# canboard.net
KiCad netlist of a schematic drawn in EAGLE
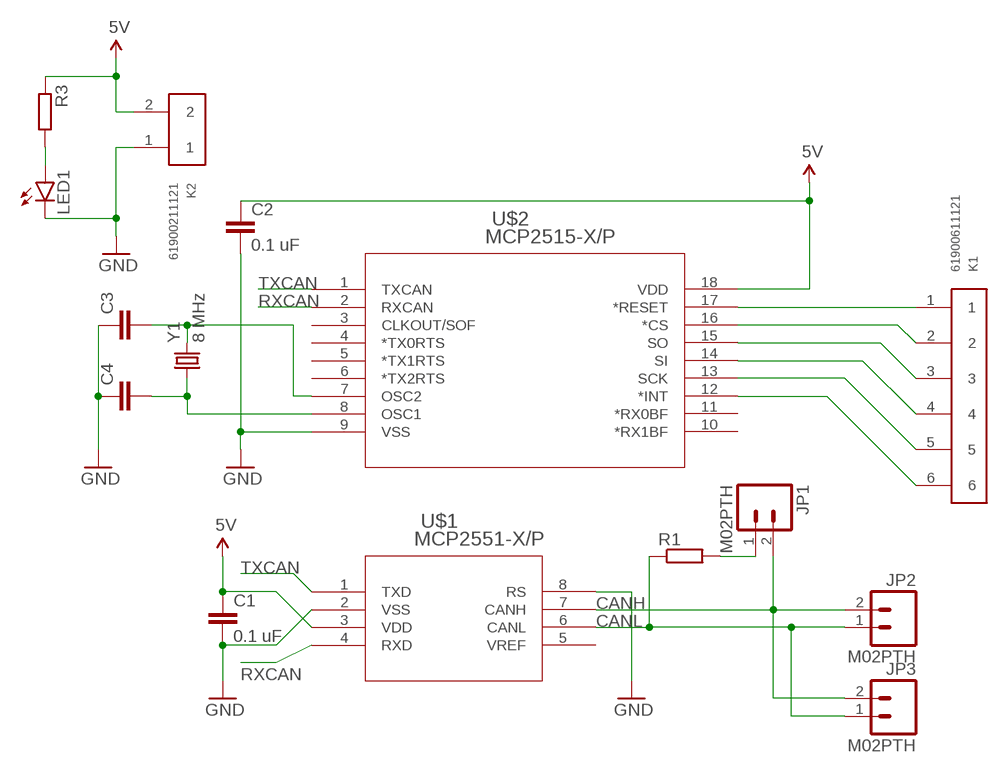
[diagram p0: schematic, sheet 1]

(export (version "E")
  (design (tool "Eeschema 10.0.6"))
  (components
    (comp (ref "C1")
      (value "0.1 uF")
      (footprint "eagle-import:C050-030X075")
      (libsource (lib "eagle-import") (part "C-EU050-030X075"))
    )
    (comp (ref "C2")
      (value "0.1 uF")
      (footprint "eagle-import:C050-030X075")
      (libsource (lib "eagle-import") (part "C-EU050-030X075"))
    )
    (comp (ref "C3")
      (value "C-EU025-025X050")
      (footprint "eagle-import:C025-025X050")
      (libsource (lib "eagle-import") (part "C-EU025-025X050"))
    )
    (comp (ref "C4")
      (value "C-EU025-025X050")
      (footprint "eagle-import:C025-025X050")
      (libsource (lib "eagle-import") (part "C-EU025-025X050"))
    )
    (comp (ref "JP1")
      (value "M02PTH")
      (footprint "eagle-import:1X02")
      (libsource (lib "eagle-import") (part "M02PTH"))
    )
    (comp (ref "JP2")
      (value "M02PTH")
      (footprint "eagle-import:1X02")
      (libsource (lib "eagle-import") (part "M02PTH"))
    )
    (comp (ref "JP3")
      (value "M02PTH")
      (footprint "eagle-import:1X02")
      (libsource (lib "eagle-import") (part "M02PTH"))
    )
    (comp (ref "K1")
      (value "61900611121")
      (footprint "eagle-import:61900611121")
      (libsource (lib "eagle-import") (part "61900611121"))
    )
    (comp (ref "K2")
      (value "61900211121")
      (footprint "eagle-import:61900211121")
      (libsource (lib "eagle-import") (part "61900211121"))
    )
    (comp (ref "LED1")
      (value "LED3MM")
      (footprint "eagle-import:LED3MM")
      (libsource (lib "eagle-import") (part "LED3MM"))
    )
    (comp (ref "R1")
      (value "R-EU_0207/10")
      (footprint "eagle-import:0207_10")
      (libsource (lib "eagle-import") (part "R-EU_0207/10"))
    )
    (comp (ref "R3")
      (value "R-EU_0207/10")
      (footprint "eagle-import:0207_10")
      (libsource (lib "eagle-import") (part "R-EU_0207/10"))
    )
    (comp (ref "U$1")
      (value "MCP2551-X/P")
      (footprint "eagle-import:PDIP8_300MC")
      (libsource (lib "eagle-import") (part "MCP2551-X/P"))
    )
    (comp (ref "U$2")
      (value "MCP2515-X/P")
      (footprint "eagle-import:PDIP18_300MC")
      (libsource (lib "eagle-import") (part "MCP2515-X/P"))
    )
    (comp (ref "Y1")
      (value "8 MHz")
      (footprint "eagle-import:HC49US")
      (libsource (lib "eagle-import") (part "CRYSTALHC49US"))
    )
  )
  (nets
    (net (code "1") (name "/CANH") (class "Default")
      (node (ref "JP1") (pin "2") (pinfunction "2_2") (pintype "passive"))
      (node (ref "JP2") (pin "2") (pinfunction "2_2") (pintype "passive"))
      (node (ref "JP3") (pin "2") (pinfunction "2_2") (pintype "passive"))
      (node (ref "U$1") (pin "7") (pinfunction "CANH_7") (pintype "passive"))
    )
    (net (code "2") (name "/CANL") (class "Default")
      (node (ref "JP2") (pin "1") (pinfunction "1_1") (pintype "passive"))
      (node (ref "JP3") (pin "1") (pinfunction "1_1") (pintype "passive"))
      (node (ref "R1") (pin "1") (pinfunction "1_1") (pintype "passive"))
      (node (ref "U$1") (pin "6") (pinfunction "CANL_6") (pintype "passive"))
    )
    (net (code "3") (name "/RXCAN") (class "Default")
      (node (ref "U$1") (pin "4") (pinfunction "RXD_4") (pintype "passive"))
      (node (ref "U$2") (pin "2") (pinfunction "RXCAN_2") (pintype "passive"))
    )
    (net (code "4") (name "/TXCAN") (class "Default")
      (node (ref "U$1") (pin "1") (pinfunction "TXD_1") (pintype "passive"))
      (node (ref "U$2") (pin "1") (pinfunction "TXCAN_1") (pintype "passive"))
    )
    (net (code "5") (name "5V") (class "Default")
      (node (ref "C1") (pin "1") (pinfunction "1_1") (pintype "passive"))
      (node (ref "C2") (pin "1") (pinfunction "1_1") (pintype "passive"))
      (node (ref "K2") (pin "2") (pinfunction "2_2") (pintype "bidirectional"))
      (node (ref "R3") (pin "1") (pinfunction "1_1") (pintype "passive"))
      (node (ref "U$1") (pin "3") (pinfunction "VDD_3") (pintype "passive"))
      (node (ref "U$2") (pin "18") (pinfunction "VDD_18") (pintype "passive"))
    )
    (net (code "6") (name "GND") (class "Default")
      (node (ref "C1") (pin "2") (pinfunction "2_2") (pintype "passive"))
      (node (ref "C2") (pin "2") (pinfunction "2_2") (pintype "passive"))
      (node (ref "C3") (pin "1") (pinfunction "1_1") (pintype "passive"))
      (node (ref "C4") (pin "1") (pinfunction "1_1") (pintype "passive"))
      (node (ref "K2") (pin "1") (pinfunction "1_1") (pintype "bidirectional"))
      (node (ref "LED1") (pin "K") (pinfunction "C_K") (pintype "passive"))
      (node (ref "U$1") (pin "2") (pinfunction "VSS_2") (pintype "passive"))
      (node (ref "U$1") (pin "8") (pinfunction "RS_8") (pintype "passive"))
      (node (ref "U$2") (pin "9") (pinfunction "VSS_9") (pintype "passive"))
    )
    (net (code "7") (name "Net-(JP1-Pad1)") (class "Default")
      (node (ref "JP1") (pin "1") (pinfunction "1_1") (pintype "passive"))
      (node (ref "R1") (pin "2") (pinfunction "2_2") (pintype "passive"))
    )
    (net (code "8") (name "Net-(LED1-PadA)") (class "Default")
      (node (ref "LED1") (pin "A") (pinfunction "A_A") (pintype "passive"))
      (node (ref "R3") (pin "2") (pinfunction "2_2") (pintype "passive"))
    )
    (net (code "9") (name "Net-(U$2-*CS)") (class "Default")
      (node (ref "K1") (pin "2") (pinfunction "2_2") (pintype "bidirectional"))
      (node (ref "U$2") (pin "16") (pinfunction "*CS_16") (pintype "passive"))
    )
    (net (code "10") (name "Net-(U$2-*INT)") (class "Default")
      (node (ref "K1") (pin "6") (pinfunction "6_6") (pintype "bidirectional"))
      (node (ref "U$2") (pin "12") (pinfunction "*INT_12") (pintype "passive"))
    )
    (net (code "11") (name "Net-(U$2-*RESET)") (class "Default")
      (node (ref "K1") (pin "1") (pinfunction "1_1") (pintype "bidirectional"))
      (node (ref "U$2") (pin "17") (pinfunction "*RESET_17") (pintype "passive"))
    )
    (net (code "12") (name "Net-(U$2-OSC1)") (class "Default")
      (node (ref "C4") (pin "2") (pinfunction "2_2") (pintype "passive"))
      (node (ref "U$2") (pin "8") (pinfunction "OSC1_8") (pintype "passive"))
      (node (ref "Y1") (pin "1") (pinfunction "1_1") (pintype "passive"))
    )
    (net (code "13") (name "Net-(U$2-OSC2)") (class "Default")
      (node (ref "C3") (pin "2") (pinfunction "2_2") (pintype "passive"))
      (node (ref "U$2") (pin "7") (pinfunction "OSC2_7") (pintype "passive"))
      (node (ref "Y1") (pin "2") (pinfunction "2_2") (pintype "passive"))
    )
    (net (code "14") (name "Net-(U$2-SCK)") (class "Default")
      (node (ref "K1") (pin "5") (pinfunction "5_5") (pintype "bidirectional"))
      (node (ref "U$2") (pin "13") (pinfunction "SCK_13") (pintype "passive"))
    )
    (net (code "15") (name "Net-(U$2-SI)") (class "Default")
      (node (ref "K1") (pin "4") (pinfunction "4_4") (pintype "bidirectional"))
      (node (ref "U$2") (pin "14") (pinfunction "SI_14") (pintype "passive"))
    )
    (net (code "16") (name "Net-(U$2-SO)") (class "Default")
      (node (ref "K1") (pin "3") (pinfunction "3_3") (pintype "bidirectional"))
      (node (ref "U$2") (pin "15") (pinfunction "SO_15") (pintype "passive"))
    )
    (net (code "17") (name "unconnected-(U$1-VREF-Pad5)") (class "Default")
      (node (ref "U$1") (pin "5") (pinfunction "VREF_5") (pintype "passive"))
    )
    (net (code "18") (name "unconnected-(U$2-*RX0BF-Pad11)") (class "Default")
      (node (ref "U$2") (pin "11") (pinfunction "*RX0BF_11") (pintype "passive"))
    )
    (net (code "19") (name "unconnected-(U$2-*RX1BF-Pad10)") (class "Default")
      (node (ref "U$2") (pin "10") (pinfunction "*RX1BF_10") (pintype "passive"))
    )
    (net (code "20") (name "unconnected-(U$2-*TX0RTS-Pad4)") (class "Default")
      (node (ref "U$2") (pin "4") (pinfunction "*TX0RTS_4") (pintype "passive"))
    )
    (net (code "21") (name "unconnected-(U$2-*TX1RTS-Pad5)") (class "Default")
      (node (ref "U$2") (pin "5") (pinfunction "*TX1RTS_5") (pintype "passive"))
    )
    (net (code "22") (name "unconnected-(U$2-*TX2RTS-Pad6)") (class "Default")
      (node (ref "U$2") (pin "6") (pinfunction "*TX2RTS_6") (pintype "passive"))
    )
    (net (code "23") (name "unconnected-(U$2-CLKOUT{slash}SOF-Pad3)") (class "Default")
      (node (ref "U$2") (pin "3") (pinfunction "CLKOUT/SOF_3") (pintype "passive"))
    )
  )
)
